# powersupply.net
KiCad netlist of a schematic drawn in Altium Designer
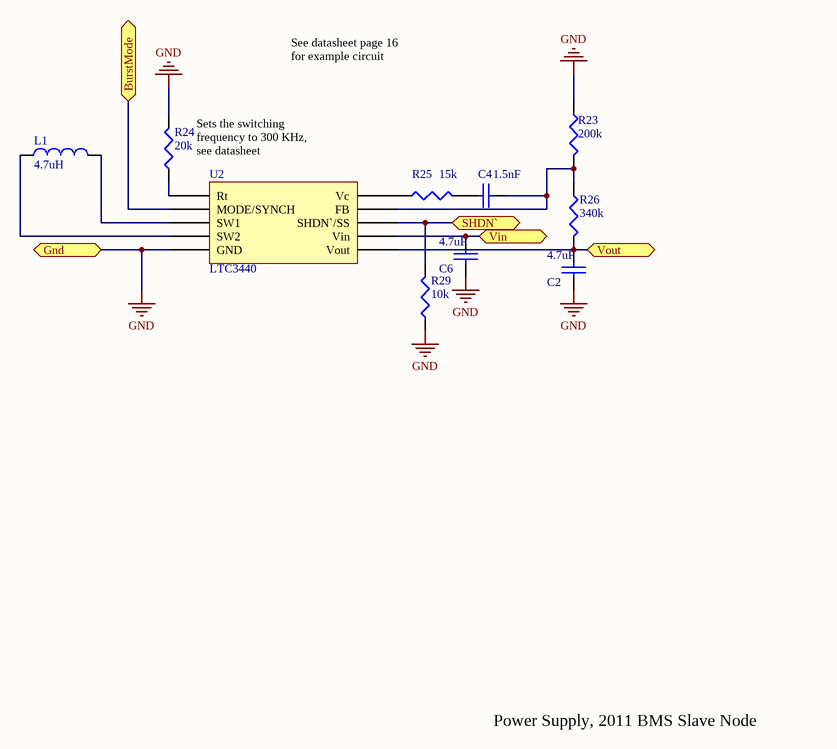
[diagram p0: powersupply.SchDoc]

(export (version "E")
  (design (tool "Eeschema 10.0.6"))
  (components
    (comp (ref "C2")
      (value "4.7uF")
      (footprint "0805")
      (description "Capacitor")
      (libsource (lib "*") (part "CAP"))
    )
    (comp (ref "C4")
      (value "1.5nF")
      (footprint "0603")
      (description "Capacitor")
      (libsource (lib "*") (part "CAP"))
    )
    (comp (ref "C6")
      (value "4.7uF")
      (footprint "0805")
      (description "Capacitor")
      (libsource (lib "*") (part "CAP"))
    )
    (comp (ref "L1")
      (value "4.7uH")
      (footprint "1812")
      (description "Inductor")
      (libsource (lib "Miscellaneous Devices") (part "Inductor"))
    )
    (comp (ref "R23")
      (value "200k")
      (footprint "0603")
      (description "Resistor")
      (libsource (lib "RCLDQ") (part "RES1"))
    )
    (comp (ref "R24")
      (value "20k")
      (footprint "0603")
      (description "Resistor")
      (libsource (lib "RCLDQ") (part "RES1"))
    )
    (comp (ref "R25")
      (value "15k")
      (footprint "0603")
      (description "Resistor")
      (libsource (lib "RCLDQ") (part "RES1"))
    )
    (comp (ref "R26")
      (value "340k")
      (footprint "0603")
      (description "Resistor")
      (libsource (lib "RCLDQ") (part "RES1"))
    )
    (comp (ref "R29")
      (value "10k")
      (footprint "0603")
      (description "Resistor")
      (libsource (lib "RCLDQ") (part "RES1"))
    )
    (comp (ref "U2") (value "LTC3440") (footprint "MSOP10") (libsource (lib "BMS") (part "LTC3440")))
  )
  (nets
    (net (code "1") (name "/BurstMode") (class "Default")
      (node (ref "U2") (pin "2") (pinfunction "MODE/SYNCH_2") (pintype "passive"))
    )
    (net (code "2") (name "/SHDN`") (class "Default")
      (node (ref "R29") (pin "2") (pinfunction "2_2") (pintype "passive"))
      (node (ref "U2") (pin "8") (pinfunction "SHDN`/SS_8") (pintype "passive"))
    )
    (net (code "3") (name "/Vin") (class "Default")
      (node (ref "C6") (pin "1") (pinfunction "1_1") (pintype "passive"))
      (node (ref "U2") (pin "7") (pinfunction "Vin_7") (pintype "passive"))
    )
    (net (code "4") (name "/Vout") (class "Default")
      (node (ref "C2") (pin "1") (pinfunction "1_1") (pintype "passive"))
      (node (ref "R26") (pin "2") (pinfunction "2_2") (pintype "passive"))
      (node (ref "U2") (pin "6") (pinfunction "Vout_6") (pintype "passive"))
    )
    (net (code "5") (name "GND") (class "Default")
      (node (ref "C2") (pin "2") (pinfunction "2_2") (pintype "passive"))
      (node (ref "C6") (pin "2") (pinfunction "2_2") (pintype "passive"))
      (node (ref "R23") (pin "1") (pinfunction "1_1") (pintype "passive"))
      (node (ref "R24") (pin "2") (pinfunction "2_2") (pintype "passive"))
      (node (ref "R29") (pin "1") (pinfunction "1_1") (pintype "passive"))
      (node (ref "U2") (pin "5") (pinfunction "GND_5") (pintype "passive"))
    )
    (net (code "6") (name "Net-(C4-Pad1)") (class "Default")
      (node (ref "C4") (pin "1") (pinfunction "1_1") (pintype "passive"))
      (node (ref "R25") (pin "2") (pinfunction "2_2") (pintype "passive"))
    )
    (net (code "7") (name "Net-(U2-FB)") (class "Default")
      (node (ref "C4") (pin "2") (pinfunction "2_2") (pintype "passive"))
      (node (ref "R23") (pin "2") (pinfunction "2_2") (pintype "passive"))
      (node (ref "R26") (pin "1") (pinfunction "1_1") (pintype "passive"))
      (node (ref "U2") (pin "9") (pinfunction "FB_9") (pintype "passive"))
    )
    (net (code "8") (name "Net-(U2-Rt)") (class "Default")
      (node (ref "R24") (pin "1") (pinfunction "1_1") (pintype "passive"))
      (node (ref "U2") (pin "1") (pinfunction "Rt_1") (pintype "passive"))
    )
    (net (code "9") (name "Net-(U2-SW1)") (class "Default")
      (node (ref "L1") (pin "2") (pinfunction "2_2") (pintype "passive"))
      (node (ref "U2") (pin "3") (pinfunction "SW1_3") (pintype "passive"))
    )
    (net (code "10") (name "Net-(U2-SW2)") (class "Default")
      (node (ref "L1") (pin "1") (pinfunction "1_1") (pintype "passive"))
      (node (ref "U2") (pin "4") (pinfunction "SW2_4") (pintype "passive"))
    )
    (net (code "11") (name "Net-(U2-Vc)") (class "Default")
      (node (ref "R25") (pin "1") (pinfunction "1_1") (pintype "passive"))
      (node (ref "U2") (pin "10") (pinfunction "Vc_10") (pintype "passive"))
    )
  )
)
